# tablespoon-no-adc.net
KiCad netlist of a schematic drawn in EAGLE
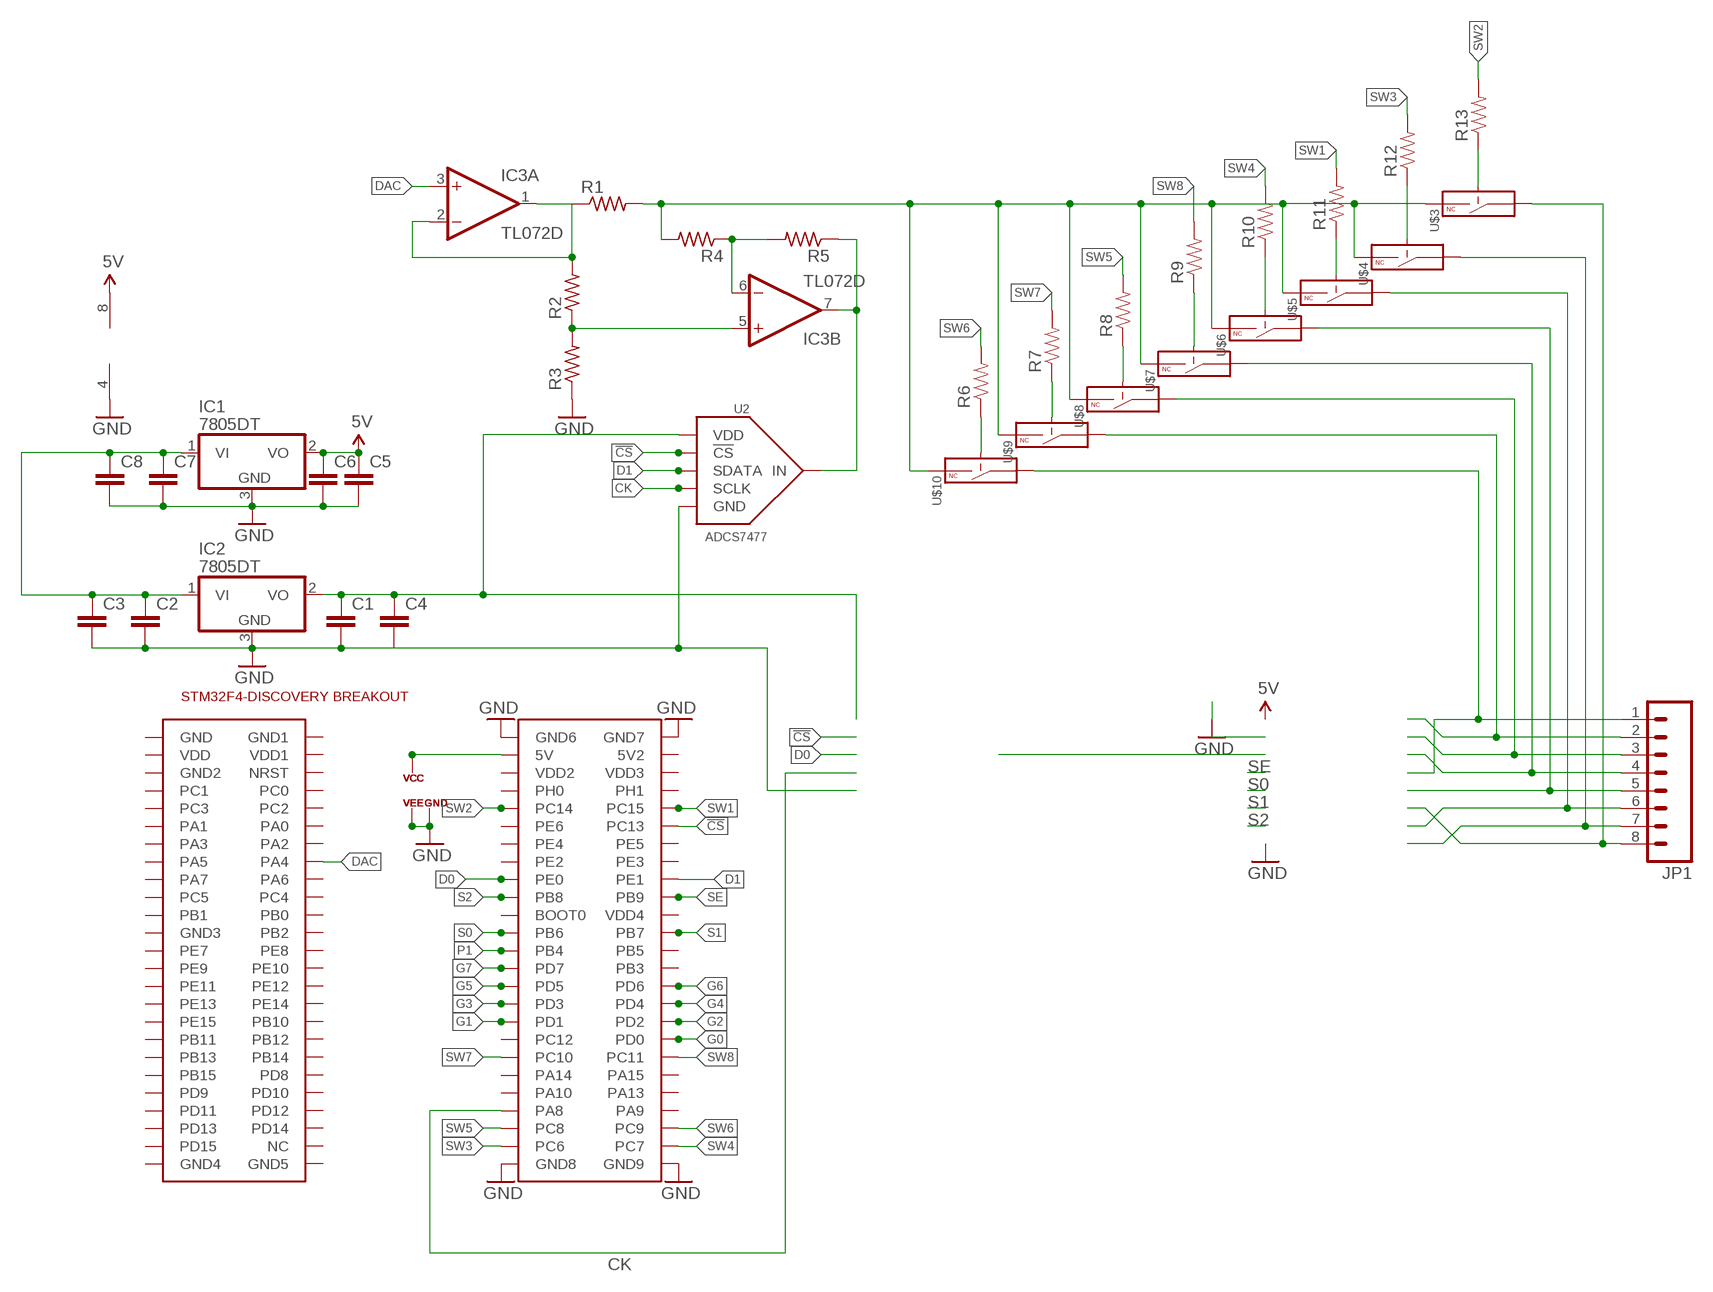
[diagram p0: schematic, sheet 1]

(export (version "E")
  (design (tool "Eeschema 10.0.6"))
  (components
    (comp (ref "C1")
      (value "C-EUC0805")
      (footprint "eagle-import:C0805")
      (libsource (lib "eagle-import") (part "C-EUC0805"))
    )
    (comp (ref "C2")
      (value "C-EUC0805")
      (footprint "eagle-import:C0805")
      (libsource (lib "eagle-import") (part "C-EUC0805"))
    )
    (comp (ref "C3")
      (value "C-EUC0805")
      (footprint "eagle-import:C0805")
      (libsource (lib "eagle-import") (part "C-EUC0805"))
    )
    (comp (ref "C4")
      (value "C-EUC0805")
      (footprint "eagle-import:C0805")
      (libsource (lib "eagle-import") (part "C-EUC0805"))
    )
    (comp (ref "C5")
      (value "C-EUC0805")
      (footprint "eagle-import:C0805")
      (libsource (lib "eagle-import") (part "C-EUC0805"))
    )
    (comp (ref "C6")
      (value "C-EUC0805")
      (footprint "eagle-import:C0805")
      (libsource (lib "eagle-import") (part "C-EUC0805"))
    )
    (comp (ref "C7")
      (value "C-EUC0805")
      (footprint "eagle-import:C0805")
      (libsource (lib "eagle-import") (part "C-EUC0805"))
    )
    (comp (ref "C8")
      (value "C-EUC0805")
      (footprint "eagle-import:C0805")
      (libsource (lib "eagle-import") (part "C-EUC0805"))
    )
    (comp (ref "IC1")
      (value "7805DT")
      (footprint "eagle-import:TO252")
      (libsource (lib "eagle-import") (part "78DT05"))
    )
    (comp (ref "IC2")
      (value "7805DT")
      (footprint "eagle-import:TO252")
      (libsource (lib "eagle-import") (part "78DT05"))
    )
    (comp (ref "IC3")
      (value "TL072D")
      (footprint "eagle-import:SO08")
      (libsource (lib "eagle-import") (part "TL072D"))
    )
    (comp (ref "JP1")
      (value "M08LONGPADS")
      (footprint "eagle-import:1X08_LONGPADS")
      (libsource (lib "eagle-import") (part "M08LONGPADS"))
    )
    (comp (ref "R1")
      (value "R-US_R0603")
      (footprint "eagle-import:R0603")
      (libsource (lib "eagle-import") (part "R-US_R0603"))
    )
    (comp (ref "R2")
      (value "R-US_R0603")
      (footprint "eagle-import:R0603")
      (libsource (lib "eagle-import") (part "R-US_R0603"))
    )
    (comp (ref "R3")
      (value "R-US_R0603")
      (footprint "eagle-import:R0603")
      (libsource (lib "eagle-import") (part "R-US_R0603"))
    )
    (comp (ref "R4")
      (value "R-US_R0603")
      (footprint "eagle-import:R0603")
      (libsource (lib "eagle-import") (part "R-US_R0603"))
    )
    (comp (ref "R5")
      (value "R-US_R0603")
      (footprint "eagle-import:R0603")
      (libsource (lib "eagle-import") (part "R-US_R0603"))
    )
    (comp (ref "R6")
      (value "RESISTOR0805-RES")
      (footprint "eagle-import:0805")
      (libsource (lib "eagle-import") (part "RESISTOR0805-RES"))
    )
    (comp (ref "R7")
      (value "RESISTOR0805-RES")
      (footprint "eagle-import:0805")
      (libsource (lib "eagle-import") (part "RESISTOR0805-RES"))
    )
    (comp (ref "R8")
      (value "RESISTOR0805-RES")
      (footprint "eagle-import:0805")
      (libsource (lib "eagle-import") (part "RESISTOR0805-RES"))
    )
    (comp (ref "R9")
      (value "RESISTOR0805-RES")
      (footprint "eagle-import:0805")
      (libsource (lib "eagle-import") (part "RESISTOR0805-RES"))
    )
    (comp (ref "R10")
      (value "RESISTOR0805-RES")
      (footprint "eagle-import:0805")
      (libsource (lib "eagle-import") (part "RESISTOR0805-RES"))
    )
    (comp (ref "R11")
      (value "RESISTOR0805-RES")
      (footprint "eagle-import:0805")
      (libsource (lib "eagle-import") (part "RESISTOR0805-RES"))
    )
    (comp (ref "R12")
      (value "RESISTOR0805-RES")
      (footprint "eagle-import:0805")
      (libsource (lib "eagle-import") (part "RESISTOR0805-RES"))
    )
    (comp (ref "R13")
      (value "RESISTOR0805-RES")
      (footprint "eagle-import:0805")
      (libsource (lib "eagle-import") (part "RESISTOR0805-RES"))
    )
    (comp (ref "U$1")
      (value "STM32F4-DISCOVERY")
      (footprint "eagle-import:STM32F4-DISCOVERY")
      (libsource (lib "eagle-import") (part "STM32F4-DISCOVERY"))
    )
    (comp (ref "U$3")
      (value "DG467")
      (footprint "eagle-import:TSSOP-6")
      (libsource (lib "eagle-import") (part "DG467"))
    )
    (comp (ref "U$4")
      (value "DG467")
      (footprint "eagle-import:TSSOP-6")
      (libsource (lib "eagle-import") (part "DG467"))
    )
    (comp (ref "U$5")
      (value "DG467")
      (footprint "eagle-import:TSSOP-6")
      (libsource (lib "eagle-import") (part "DG467"))
    )
    (comp (ref "U$6")
      (value "DG467")
      (footprint "eagle-import:TSSOP-6")
      (libsource (lib "eagle-import") (part "DG467"))
    )
    (comp (ref "U$7")
      (value "DG467")
      (footprint "eagle-import:TSSOP-6")
      (libsource (lib "eagle-import") (part "DG467"))
    )
    (comp (ref "U$8")
      (value "DG467")
      (footprint "eagle-import:TSSOP-6")
      (libsource (lib "eagle-import") (part "DG467"))
    )
    (comp (ref "U$9")
      (value "DG467")
      (footprint "eagle-import:TSSOP-6")
      (libsource (lib "eagle-import") (part "DG467"))
    )
    (comp (ref "U$10")
      (value "DG467")
      (footprint "eagle-import:TSSOP-6")
      (libsource (lib "eagle-import") (part "DG467"))
    )
    (comp (ref "U2")
      (value "ADCS7477")
      (footprint "eagle-import:SOT-23-6")
      (libsource (lib "eagle-import") (part "ADCS7477"))
    )
  )
  (nets
    (net (code "1") (name "/~{CS}") (class "Default")
      (node (ref "U$1") (pin "P$62") (pinfunction "PC13_P$62") (pintype "bidirectional"))
      (node (ref "U2") (pin "P$6") (pinfunction "~{CS}_P$6") (pintype "bidirectional"))
    )
    (net (code "2") (name "5V") (class "Default")
      (node (ref "C5") (pin "1") (pinfunction "1_1") (pintype "passive"))
      (node (ref "C6") (pin "1") (pinfunction "1_1") (pintype "passive"))
      (node (ref "IC1") (pin "2") (pinfunction "VO_2") (pintype "passive"))
      (node (ref "IC3") (pin "8") (pinfunction "V+_8") (pintype "power_in"))
    )
    (net (code "3") (name "CK") (class "Default")
      (node (ref "U$1") (pin "P$93") (pinfunction "PA8_P$93") (pintype "bidirectional"))
      (node (ref "U2") (pin "P$4") (pinfunction "SCLK_P$4") (pintype "bidirectional"))
    )
    (net (code "4") (name "D0") (class "Default")
      (node (ref "U$1") (pin "P$67") (pinfunction "PE0_P$67") (pintype "bidirectional"))
    )
    (net (code "5") (name "D1") (class "Default")
      (node (ref "U$1") (pin "P$68") (pinfunction "PE1_P$68") (pintype "bidirectional"))
      (node (ref "U2") (pin "P$5") (pinfunction "SDATA_P$5") (pintype "bidirectional"))
    )
    (net (code "6") (name "DAC") (class "Default")
      (node (ref "IC3") (pin "3") (pinfunction "+IN_3") (pintype "input"))
      (node (ref "U$1") (pin "P$16") (pinfunction "PA4_P$16") (pintype "bidirectional"))
    )
    (net (code "7") (name "G0") (class "Default")
      (node (ref "U$1") (pin "P$86") (pinfunction "PD0_P$86") (pintype "bidirectional"))
    )
    (net (code "8") (name "G1") (class "Default")
      (node (ref "U$1") (pin "P$83") (pinfunction "PD1_P$83") (pintype "bidirectional"))
    )
    (net (code "9") (name "G2") (class "Default")
      (node (ref "U$1") (pin "P$84") (pinfunction "PD2_P$84") (pintype "bidirectional"))
    )
    (net (code "10") (name "G3") (class "Default")
      (node (ref "U$1") (pin "P$81") (pinfunction "PD3_P$81") (pintype "bidirectional"))
    )
    (net (code "11") (name "G4") (class "Default")
      (node (ref "U$1") (pin "P$82") (pinfunction "PD4_P$82") (pintype "bidirectional"))
    )
    (net (code "12") (name "G5") (class "Default")
      (node (ref "U$1") (pin "P$79") (pinfunction "PD5_P$79") (pintype "bidirectional"))
    )
    (net (code "13") (name "G6") (class "Default")
      (node (ref "U$1") (pin "P$80") (pinfunction "PD6_P$80") (pintype "bidirectional"))
    )
    (net (code "14") (name "G7") (class "Default")
      (node (ref "U$1") (pin "P$77") (pinfunction "PD7_P$77") (pintype "bidirectional"))
    )
    (net (code "15") (name "GND") (class "Default")
      (node (ref "C1") (pin "2") (pinfunction "2_2") (pintype "passive"))
      (node (ref "C2") (pin "2") (pinfunction "2_2") (pintype "passive"))
      (node (ref "C3") (pin "2") (pinfunction "2_2") (pintype "passive"))
      (node (ref "C4") (pin "2") (pinfunction "2_2") (pintype "passive"))
      (node (ref "C5") (pin "2") (pinfunction "2_2") (pintype "passive"))
      (node (ref "C6") (pin "2") (pinfunction "2_2") (pintype "passive"))
      (node (ref "C7") (pin "2") (pinfunction "2_2") (pintype "passive"))
      (node (ref "C8") (pin "2") (pinfunction "2_2") (pintype "passive"))
      (node (ref "IC1") (pin "3") (pinfunction "GND_3") (pintype "passive"))
      (node (ref "IC2") (pin "3") (pinfunction "GND_3") (pintype "passive"))
      (node (ref "IC3") (pin "4") (pinfunction "V-_4") (pintype "power_in"))
      (node (ref "R3") (pin "1") (pinfunction "1_1") (pintype "passive"))
      (node (ref "U$1") (pin "P$100") (pinfunction "GND9_P$100") (pintype "bidirectional"))
      (node (ref "U$1") (pin "P$51") (pinfunction "GND6_P$51") (pintype "bidirectional"))
      (node (ref "U$1") (pin "P$52") (pinfunction "GND7_P$52") (pintype "bidirectional"))
      (node (ref "U$1") (pin "P$99") (pinfunction "GND8_P$99") (pintype "bidirectional"))
      (node (ref "U$10") (pin "P$2") (pinfunction "VEE_P$2") (pintype "bidirectional"))
      (node (ref "U$10") (pin "P$4") (pinfunction "GND_P$4") (pintype "bidirectional"))
      (node (ref "U$3") (pin "P$2") (pinfunction "VEE_P$2") (pintype "bidirectional"))
      (node (ref "U$3") (pin "P$4") (pinfunction "GND_P$4") (pintype "bidirectional"))
      (node (ref "U$4") (pin "P$2") (pinfunction "VEE_P$2") (pintype "bidirectional"))
      (node (ref "U$4") (pin "P$4") (pinfunction "GND_P$4") (pintype "bidirectional"))
      (node (ref "U$5") (pin "P$2") (pinfunction "VEE_P$2") (pintype "bidirectional"))
      (node (ref "U$5") (pin "P$4") (pinfunction "GND_P$4") (pintype "bidirectional"))
      (node (ref "U$6") (pin "P$2") (pinfunction "VEE_P$2") (pintype "bidirectional"))
      (node (ref "U$6") (pin "P$4") (pinfunction "GND_P$4") (pintype "bidirectional"))
      (node (ref "U$7") (pin "P$2") (pinfunction "VEE_P$2") (pintype "bidirectional"))
      (node (ref "U$7") (pin "P$4") (pinfunction "GND_P$4") (pintype "bidirectional"))
      (node (ref "U$8") (pin "P$2") (pinfunction "VEE_P$2") (pintype "bidirectional"))
      (node (ref "U$8") (pin "P$4") (pinfunction "GND_P$4") (pintype "bidirectional"))
      (node (ref "U$9") (pin "P$2") (pinfunction "VEE_P$2") (pintype "bidirectional"))
      (node (ref "U$9") (pin "P$4") (pinfunction "GND_P$4") (pintype "bidirectional"))
      (node (ref "U2") (pin "P$2") (pinfunction "GND_P$2") (pintype "bidirectional"))
    )
    (net (code "16") (name "Net-(IC1-VI)") (class "Default")
      (node (ref "C2") (pin "1") (pinfunction "1_1") (pintype "passive"))
      (node (ref "C3") (pin "1") (pinfunction "1_1") (pintype "passive"))
      (node (ref "C7") (pin "1") (pinfunction "1_1") (pintype "passive"))
      (node (ref "C8") (pin "1") (pinfunction "1_1") (pintype "passive"))
      (node (ref "IC1") (pin "1") (pinfunction "VI_1") (pintype "input"))
      (node (ref "IC2") (pin "1") (pinfunction "VI_1") (pintype "input"))
    )
    (net (code "17") (name "Net-(IC2-VO)") (class "Default")
      (node (ref "C1") (pin "1") (pinfunction "1_1") (pintype "passive"))
      (node (ref "C4") (pin "1") (pinfunction "1_1") (pintype "passive"))
      (node (ref "IC2") (pin "2") (pinfunction "VO_2") (pintype "passive"))
      (node (ref "U2") (pin "P$1") (pinfunction "VDD_P$1") (pintype "bidirectional"))
    )
    (net (code "18") (name "Net-(IC3A--IN)") (class "Default")
      (node (ref "IC3") (pin "1") (pinfunction "OUT_1") (pintype "output"))
      (node (ref "IC3") (pin "2") (pinfunction "-IN_2") (pintype "input"))
      (node (ref "R1") (pin "1") (pinfunction "1_1") (pintype "passive"))
      (node (ref "R2") (pin "2") (pinfunction "2_2") (pintype "passive"))
    )
    (net (code "19") (name "Net-(IC3B-+IN)") (class "Default")
      (node (ref "IC3") (pin "5") (pinfunction "+IN_5") (pintype "input"))
      (node (ref "R2") (pin "1") (pinfunction "1_1") (pintype "passive"))
      (node (ref "R3") (pin "2") (pinfunction "2_2") (pintype "passive"))
    )
    (net (code "20") (name "Net-(IC3B--IN)") (class "Default")
      (node (ref "IC3") (pin "6") (pinfunction "-IN_6") (pintype "input"))
      (node (ref "R4") (pin "1") (pinfunction "1_1") (pintype "passive"))
      (node (ref "R5") (pin "2") (pinfunction "2_2") (pintype "passive"))
    )
    (net (code "21") (name "Net-(IC3B-OUT)") (class "Default")
      (node (ref "IC3") (pin "7") (pinfunction "OUT_7") (pintype "output"))
      (node (ref "R5") (pin "1") (pinfunction "1_1") (pintype "passive"))
      (node (ref "U2") (pin "P$3") (pinfunction "IN_P$3") (pintype "bidirectional"))
    )
    (net (code "22") (name "Net-(U$1-5V)") (class "Default")
      (node (ref "U$1") (pin "P$53") (pinfunction "5V_P$53") (pintype "bidirectional"))
      (node (ref "U$10") (pin "P$5") (pinfunction "VCC_P$5") (pintype "bidirectional"))
      (node (ref "U$3") (pin "P$5") (pinfunction "VCC_P$5") (pintype "bidirectional"))
      (node (ref "U$4") (pin "P$5") (pinfunction "VCC_P$5") (pintype "bidirectional"))
      (node (ref "U$5") (pin "P$5") (pinfunction "VCC_P$5") (pintype "bidirectional"))
      (node (ref "U$6") (pin "P$5") (pinfunction "VCC_P$5") (pintype "bidirectional"))
      (node (ref "U$7") (pin "P$5") (pinfunction "VCC_P$5") (pintype "bidirectional"))
      (node (ref "U$8") (pin "P$5") (pinfunction "VCC_P$5") (pintype "bidirectional"))
      (node (ref "U$9") (pin "P$5") (pinfunction "VCC_P$5") (pintype "bidirectional"))
    )
    (net (code "23") (name "Net-(U$3A-COM)") (class "Default")
      (node (ref "JP1") (pin "8") (pinfunction "8_8") (pintype "passive"))
      (node (ref "U$3") (pin "P$6") (pinfunction "COM_P$6") (pintype "bidirectional"))
    )
    (net (code "24") (name "Net-(U$3A-CTL)") (class "Default")
      (node (ref "R13") (pin "1") (pinfunction "1_1") (pintype "passive"))
      (node (ref "U$3") (pin "P$3") (pinfunction "CTL_P$3") (pintype "bidirectional"))
    )
    (net (code "25") (name "Net-(U$4A-COM)") (class "Default")
      (node (ref "JP1") (pin "7") (pinfunction "7_7") (pintype "passive"))
      (node (ref "U$4") (pin "P$6") (pinfunction "COM_P$6") (pintype "bidirectional"))
    )
    (net (code "26") (name "Net-(U$4A-CTL)") (class "Default")
      (node (ref "R12") (pin "1") (pinfunction "1_1") (pintype "passive"))
      (node (ref "U$4") (pin "P$3") (pinfunction "CTL_P$3") (pintype "bidirectional"))
    )
    (net (code "27") (name "Net-(U$5A-COM)") (class "Default")
      (node (ref "JP1") (pin "6") (pinfunction "6_6") (pintype "passive"))
      (node (ref "U$5") (pin "P$6") (pinfunction "COM_P$6") (pintype "bidirectional"))
    )
    (net (code "28") (name "Net-(U$5A-CTL)") (class "Default")
      (node (ref "R11") (pin "1") (pinfunction "1_1") (pintype "passive"))
      (node (ref "U$5") (pin "P$3") (pinfunction "CTL_P$3") (pintype "bidirectional"))
    )
    (net (code "29") (name "Net-(U$6A-COM)") (class "Default")
      (node (ref "JP1") (pin "5") (pinfunction "5_5") (pintype "passive"))
      (node (ref "U$6") (pin "P$6") (pinfunction "COM_P$6") (pintype "bidirectional"))
    )
    (net (code "30") (name "Net-(U$6A-CTL)") (class "Default")
      (node (ref "R10") (pin "1") (pinfunction "1_1") (pintype "passive"))
      (node (ref "U$6") (pin "P$3") (pinfunction "CTL_P$3") (pintype "bidirectional"))
    )
    (net (code "31") (name "Net-(U$7A-COM)") (class "Default")
      (node (ref "JP1") (pin "4") (pinfunction "4_4") (pintype "passive"))
      (node (ref "U$7") (pin "P$6") (pinfunction "COM_P$6") (pintype "bidirectional"))
    )
    (net (code "32") (name "Net-(U$7A-CTL)") (class "Default")
      (node (ref "R9") (pin "1") (pinfunction "1_1") (pintype "passive"))
      (node (ref "U$7") (pin "P$3") (pinfunction "CTL_P$3") (pintype "bidirectional"))
    )
    (net (code "33") (name "Net-(U$8A-COM)") (class "Default")
      (node (ref "JP1") (pin "3") (pinfunction "3_3") (pintype "passive"))
      (node (ref "U$8") (pin "P$6") (pinfunction "COM_P$6") (pintype "bidirectional"))
    )
    (net (code "34") (name "Net-(U$8A-CTL)") (class "Default")
      (node (ref "R8") (pin "1") (pinfunction "1_1") (pintype "passive"))
      (node (ref "U$8") (pin "P$3") (pinfunction "CTL_P$3") (pintype "bidirectional"))
    )
    (net (code "35") (name "Net-(U$9A-COM)") (class "Default")
      (node (ref "JP1") (pin "2") (pinfunction "2_2") (pintype "passive"))
      (node (ref "U$9") (pin "P$6") (pinfunction "COM_P$6") (pintype "bidirectional"))
    )
    (net (code "36") (name "Net-(U$9A-CTL)") (class "Default")
      (node (ref "R7") (pin "1") (pinfunction "1_1") (pintype "passive"))
      (node (ref "U$9") (pin "P$3") (pinfunction "CTL_P$3") (pintype "bidirectional"))
    )
    (net (code "37") (name "Net-(U$10A-COM)") (class "Default")
      (node (ref "JP1") (pin "1") (pinfunction "1_1") (pintype "passive"))
      (node (ref "U$10") (pin "P$6") (pinfunction "COM_P$6") (pintype "bidirectional"))
    )
    (net (code "38") (name "Net-(U$10A-CTL)") (class "Default")
      (node (ref "R6") (pin "1") (pinfunction "1_1") (pintype "passive"))
      (node (ref "U$10") (pin "P$3") (pinfunction "CTL_P$3") (pintype "bidirectional"))
    )
    (net (code "39") (name "Net-(U$10A-IN)") (class "Default")
      (node (ref "R1") (pin "2") (pinfunction "2_2") (pintype "passive"))
      (node (ref "R4") (pin "2") (pinfunction "2_2") (pintype "passive"))
      (node (ref "U$10") (pin "P$1") (pinfunction "IN_P$1") (pintype "bidirectional"))
      (node (ref "U$3") (pin "P$1") (pinfunction "IN_P$1") (pintype "bidirectional"))
      (node (ref "U$4") (pin "P$1") (pinfunction "IN_P$1") (pintype "bidirectional"))
      (node (ref "U$5") (pin "P$1") (pinfunction "IN_P$1") (pintype "bidirectional"))
      (node (ref "U$6") (pin "P$1") (pinfunction "IN_P$1") (pintype "bidirectional"))
      (node (ref "U$7") (pin "P$1") (pinfunction "IN_P$1") (pintype "bidirectional"))
      (node (ref "U$8") (pin "P$1") (pinfunction "IN_P$1") (pintype "bidirectional"))
      (node (ref "U$9") (pin "P$1") (pinfunction "IN_P$1") (pintype "bidirectional"))
    )
    (net (code "40") (name "P1") (class "Default")
      (node (ref "U$1") (pin "P$75") (pinfunction "PB4_P$75") (pintype "bidirectional"))
    )
    (net (code "41") (name "S0") (class "Default")
      (node (ref "U$1") (pin "P$73") (pinfunction "PB6_P$73") (pintype "bidirectional"))
    )
    (net (code "42") (name "S1") (class "Default")
      (node (ref "U$1") (pin "P$74") (pinfunction "PB7_P$74") (pintype "bidirectional"))
    )
    (net (code "43") (name "S2") (class "Default")
      (node (ref "U$1") (pin "P$69") (pinfunction "PB8_P$69") (pintype "bidirectional"))
    )
    (net (code "44") (name "SE") (class "Default")
      (node (ref "U$1") (pin "P$70") (pinfunction "PB9_P$70") (pintype "bidirectional"))
    )
    (net (code "45") (name "SW1") (class "Default")
      (node (ref "R11") (pin "2") (pinfunction "2_2") (pintype "passive"))
      (node (ref "U$1") (pin "P$60") (pinfunction "PC15_P$60") (pintype "bidirectional"))
    )
    (net (code "46") (name "SW2") (class "Default")
      (node (ref "R13") (pin "2") (pinfunction "2_2") (pintype "passive"))
      (node (ref "U$1") (pin "P$59") (pinfunction "PC14_P$59") (pintype "bidirectional"))
    )
    (net (code "47") (name "SW3") (class "Default")
      (node (ref "R12") (pin "2") (pinfunction "2_2") (pintype "passive"))
      (node (ref "U$1") (pin "P$97") (pinfunction "PC6_P$97") (pintype "bidirectional"))
    )
    (net (code "48") (name "SW4") (class "Default")
      (node (ref "R10") (pin "2") (pinfunction "2_2") (pintype "passive"))
      (node (ref "U$1") (pin "P$98") (pinfunction "PC7_P$98") (pintype "bidirectional"))
    )
    (net (code "49") (name "SW5") (class "Default")
      (node (ref "R8") (pin "2") (pinfunction "2_2") (pintype "passive"))
      (node (ref "U$1") (pin "P$95") (pinfunction "PC8_P$95") (pintype "bidirectional"))
    )
    (net (code "50") (name "SW6") (class "Default")
      (node (ref "R6") (pin "2") (pinfunction "2_2") (pintype "passive"))
      (node (ref "U$1") (pin "P$96") (pinfunction "PC9_P$96") (pintype "bidirectional"))
    )
    (net (code "51") (name "SW7") (class "Default")
      (node (ref "R7") (pin "2") (pinfunction "2_2") (pintype "passive"))
      (node (ref "U$1") (pin "P$87") (pinfunction "PC10_P$87") (pintype "bidirectional"))
    )
    (net (code "52") (name "SW8") (class "Default")
      (node (ref "R9") (pin "2") (pinfunction "2_2") (pintype "passive"))
      (node (ref "U$1") (pin "P$88") (pinfunction "PC11_P$88") (pintype "bidirectional"))
    )
    (net (code "53") (name "unconnected-(U$1-5V2-PadP$54)") (class "Default")
      (node (ref "U$1") (pin "P$54") (pinfunction "5V2_P$54") (pintype "bidirectional"))
    )
    (net (code "54") (name "unconnected-(U$1-BOOT0-PadP$71)") (class "Default")
      (node (ref "U$1") (pin "P$71") (pinfunction "BOOT0_P$71") (pintype "bidirectional"))
    )
    (net (code "55") (name "unconnected-(U$1-GND-PadP$1)") (class "Default")
      (node (ref "U$1") (pin "P$1") (pinfunction "GND_P$1") (pintype "bidirectional"))
    )
    (net (code "56") (name "unconnected-(U$1-GND1-PadP$2)") (class "Default")
      (node (ref "U$1") (pin "P$2") (pinfunction "GND1_P$2") (pintype "bidirectional"))
    )
    (net (code "57") (name "unconnected-(U$1-GND2-PadP$5)") (class "Default")
      (node (ref "U$1") (pin "P$5") (pinfunction "GND2_P$5") (pintype "bidirectional"))
    )
    (net (code "58") (name "unconnected-(U$1-GND3-PadP$23)") (class "Default")
      (node (ref "U$1") (pin "P$23") (pinfunction "GND3_P$23") (pintype "bidirectional"))
    )
    (net (code "59") (name "unconnected-(U$1-GND4-PadP$49)") (class "Default")
      (node (ref "U$1") (pin "P$49") (pinfunction "GND4_P$49") (pintype "bidirectional"))
    )
    (net (code "60") (name "unconnected-(U$1-GND5-PadP$50)") (class "Default")
      (node (ref "U$1") (pin "P$50") (pinfunction "GND5_P$50") (pintype "bidirectional"))
    )
    (net (code "61") (name "unconnected-(U$1-NC-PadP$48)") (class "Default")
      (node (ref "U$1") (pin "P$48") (pinfunction "NC_P$48") (pintype "bidirectional"))
    )
    (net (code "62") (name "unconnected-(U$1-NRST-PadP$6)") (class "Default")
      (node (ref "U$1") (pin "P$6") (pinfunction "NRST_P$6") (pintype "bidirectional"))
    )
    (net (code "63") (name "unconnected-(U$1-PA0-PadP$12)") (class "Default")
      (node (ref "U$1") (pin "P$12") (pinfunction "PA0_P$12") (pintype "bidirectional"))
    )
    (net (code "64") (name "unconnected-(U$1-PA1-PadP$11)") (class "Default")
      (node (ref "U$1") (pin "P$11") (pinfunction "PA1_P$11") (pintype "bidirectional"))
    )
    (net (code "65") (name "unconnected-(U$1-PA2-PadP$14)") (class "Default")
      (node (ref "U$1") (pin "P$14") (pinfunction "PA2_P$14") (pintype "bidirectional"))
    )
    (net (code "66") (name "unconnected-(U$1-PA3-PadP$13)") (class "Default")
      (node (ref "U$1") (pin "P$13") (pinfunction "PA3_P$13") (pintype "bidirectional"))
    )
    (net (code "67") (name "unconnected-(U$1-PA5-PadP$15)") (class "Default")
      (node (ref "U$1") (pin "P$15") (pinfunction "PA5_P$15") (pintype "bidirectional"))
    )
    (net (code "68") (name "unconnected-(U$1-PA6-PadP$18)") (class "Default")
      (node (ref "U$1") (pin "P$18") (pinfunction "PA6_P$18") (pintype "bidirectional"))
    )
    (net (code "69") (name "unconnected-(U$1-PA7-PadP$17)") (class "Default")
      (node (ref "U$1") (pin "P$17") (pinfunction "PA7_P$17") (pintype "bidirectional"))
    )
    (net (code "70") (name "unconnected-(U$1-PA9-PadP$94)") (class "Default")
      (node (ref "U$1") (pin "P$94") (pinfunction "PA9_P$94") (pintype "bidirectional"))
    )
    (net (code "71") (name "unconnected-(U$1-PA10-PadP$91)") (class "Default")
      (node (ref "U$1") (pin "P$91") (pinfunction "PA10_P$91") (pintype "bidirectional"))
    )
    (net (code "72") (name "unconnected-(U$1-PA13-PadP$92)") (class "Default")
      (node (ref "U$1") (pin "P$92") (pinfunction "PA13_P$92") (pintype "bidirectional"))
    )
    (net (code "73") (name "unconnected-(U$1-PA14-PadP$89)") (class "Default")
      (node (ref "U$1") (pin "P$89") (pinfunction "PA14_P$89") (pintype "bidirectional"))
    )
    (net (code "74") (name "unconnected-(U$1-PA15-PadP$90)") (class "Default")
      (node (ref "U$1") (pin "P$90") (pinfunction "PA15_P$90") (pintype "bidirectional"))
    )
    (net (code "75") (name "unconnected-(U$1-PB0-PadP$22)") (class "Default")
      (node (ref "U$1") (pin "P$22") (pinfunction "PB0_P$22") (pintype "bidirectional"))
    )
    (net (code "76") (name "unconnected-(U$1-PB1-PadP$21)") (class "Default")
      (node (ref "U$1") (pin "P$21") (pinfunction "PB1_P$21") (pintype "bidirectional"))
    )
    (net (code "77") (name "unconnected-(U$1-PB2-PadP$24)") (class "Default")
      (node (ref "U$1") (pin "P$24") (pinfunction "PB2_P$24") (pintype "bidirectional"))
    )
    (net (code "78") (name "unconnected-(U$1-PB3-PadP$78)") (class "Default")
      (node (ref "U$1") (pin "P$78") (pinfunction "PB3_P$78") (pintype "bidirectional"))
    )
    (net (code "79") (name "unconnected-(U$1-PB5-PadP$76)") (class "Default")
      (node (ref "U$1") (pin "P$76") (pinfunction "PB5_P$76") (pintype "bidirectional"))
    )
    (net (code "80") (name "unconnected-(U$1-PB10-PadP$34)") (class "Default")
      (node (ref "U$1") (pin "P$34") (pinfunction "PB10_P$34") (pintype "bidirectional"))
    )
    (net (code "81") (name "unconnected-(U$1-PB11-PadP$35)") (class "Default")
      (node (ref "U$1") (pin "P$35") (pinfunction "PB11_P$35") (pintype "bidirectional"))
    )
    (net (code "82") (name "unconnected-(U$1-PB12-PadP$36)") (class "Default")
      (node (ref "U$1") (pin "P$36") (pinfunction "PB12_P$36") (pintype "bidirectional"))
    )
    (net (code "83") (name "unconnected-(U$1-PB13-PadP$37)") (class "Default")
      (node (ref "U$1") (pin "P$37") (pinfunction "PB13_P$37") (pintype "bidirectional"))
    )
    (net (code "84") (name "unconnected-(U$1-PB14-PadP$38)") (class "Default")
      (node (ref "U$1") (pin "P$38") (pinfunction "PB14_P$38") (pintype "bidirectional"))
    )
    (net (code "85") (name "unconnected-(U$1-PB15-PadP$39)") (class "Default")
      (node (ref "U$1") (pin "P$39") (pinfunction "PB15_P$39") (pintype "bidirectional"))
    )
    (net (code "86") (name "unconnected-(U$1-PC0-PadP$8)") (class "Default")
      (node (ref "U$1") (pin "P$8") (pinfunction "PC0_P$8") (pintype "bidirectional"))
    )
    (net (code "87") (name "unconnected-(U$1-PC1-PadP$7)") (class "Default")
      (node (ref "U$1") (pin "P$7") (pinfunction "PC1_P$7") (pintype "bidirectional"))
    )
    (net (code "88") (name "unconnected-(U$1-PC2-PadP$10)") (class "Default")
      (node (ref "U$1") (pin "P$10") (pinfunction "PC2_P$10") (pintype "bidirectional"))
    )
    (net (code "89") (name "unconnected-(U$1-PC3-PadP$9)") (class "Default")
      (node (ref "U$1") (pin "P$9") (pinfunction "PC3_P$9") (pintype "bidirectional"))
    )
    (net (code "90") (name "unconnected-(U$1-PC4-PadP$20)") (class "Default")
      (node (ref "U$1") (pin "P$20") (pinfunction "PC4_P$20") (pintype "bidirectional"))
    )
    (net (code "91") (name "unconnected-(U$1-PC5-PadP$19)") (class "Default")
      (node (ref "U$1") (pin "P$19") (pinfunction "PC5_P$19") (pintype "bidirectional"))
    )
    (net (code "92") (name "unconnected-(U$1-PC12-PadP$85)") (class "Default")
      (node (ref "U$1") (pin "P$85") (pinfunction "PC12_P$85") (pintype "bidirectional"))
    )
    (net (code "93") (name "unconnected-(U$1-PD8-PadP$40)") (class "Default")
      (node (ref "U$1") (pin "P$40") (pinfunction "PD8_P$40") (pintype "bidirectional"))
    )
    (net (code "94") (name "unconnected-(U$1-PD9-PadP$41)") (class "Default")
      (node (ref "U$1") (pin "P$41") (pinfunction "PD9_P$41") (pintype "bidirectional"))
    )
    (net (code "95") (name "unconnected-(U$1-PD10-PadP$42)") (class "Default")
      (node (ref "U$1") (pin "P$42") (pinfunction "PD10_P$42") (pintype "bidirectional"))
    )
    (net (code "96") (name "unconnected-(U$1-PD11-PadP$43)") (class "Default")
      (node (ref "U$1") (pin "P$43") (pinfunction "PD11_P$43") (pintype "bidirectional"))
    )
    (net (code "97") (name "unconnected-(U$1-PD12-PadP$44)") (class "Default")
      (node (ref "U$1") (pin "P$44") (pinfunction "PD12_P$44") (pintype "bidirectional"))
    )
    (net (code "98") (name "unconnected-(U$1-PD13-PadP$45)") (class "Default")
      (node (ref "U$1") (pin "P$45") (pinfunction "PD13_P$45") (pintype "bidirectional"))
    )
    (net (code "99") (name "unconnected-(U$1-PD14-PadP$46)") (class "Default")
      (node (ref "U$1") (pin "P$46") (pinfunction "PD14_P$46") (pintype "bidirectional"))
    )
    (net (code "100") (name "unconnected-(U$1-PD15-PadP$47)") (class "Default")
      (node (ref "U$1") (pin "P$47") (pinfunction "PD15_P$47") (pintype "bidirectional"))
    )
    (net (code "101") (name "unconnected-(U$1-PE2-PadP$65)") (class "Default")
      (node (ref "U$1") (pin "P$65") (pinfunction "PE2_P$65") (pintype "bidirectional"))
    )
    (net (code "102") (name "unconnected-(U$1-PE3-PadP$66)") (class "Default")
      (node (ref "U$1") (pin "P$66") (pinfunction "PE3_P$66") (pintype "bidirectional"))
    )
    (net (code "103") (name "unconnected-(U$1-PE4-PadP$63)") (class "Default")
      (node (ref "U$1") (pin "P$63") (pinfunction "PE4_P$63") (pintype "bidirectional"))
    )
    (net (code "104") (name "unconnected-(U$1-PE5-PadP$64)") (class "Default")
      (node (ref "U$1") (pin "P$64") (pinfunction "PE5_P$64") (pintype "bidirectional"))
    )
    (net (code "105") (name "unconnected-(U$1-PE6-PadP$61)") (class "Default")
      (node (ref "U$1") (pin "P$61") (pinfunction "PE6_P$61") (pintype "bidirectional"))
    )
    (net (code "106") (name "unconnected-(U$1-PE7-PadP$25)") (class "Default")
      (node (ref "U$1") (pin "P$25") (pinfunction "PE7_P$25") (pintype "bidirectional"))
    )
    (net (code "107") (name "unconnected-(U$1-PE8-PadP$26)") (class "Default")
      (node (ref "U$1") (pin "P$26") (pinfunction "PE8_P$26") (pintype "bidirectional"))
    )
    (net (code "108") (name "unconnected-(U$1-PE9-PadP$27)") (class "Default")
      (node (ref "U$1") (pin "P$27") (pinfunction "PE9_P$27") (pintype "bidirectional"))
    )
    (net (code "109") (name "unconnected-(U$1-PE10-PadP$28)") (class "Default")
      (node (ref "U$1") (pin "P$28") (pinfunction "PE10_P$28") (pintype "bidirectional"))
    )
    (net (code "110") (name "unconnected-(U$1-PE11-PadP$29)") (class "Default")
      (node (ref "U$1") (pin "P$29") (pinfunction "PE11_P$29") (pintype "bidirectional"))
    )
    (net (code "111") (name "unconnected-(U$1-PE12-PadP$30)") (class "Default")
      (node (ref "U$1") (pin "P$30") (pinfunction "PE12_P$30") (pintype "bidirectional"))
    )
    (net (code "112") (name "unconnected-(U$1-PE13-PadP$31)") (class "Default")
      (node (ref "U$1") (pin "P$31") (pinfunction "PE13_P$31") (pintype "bidirectional"))
    )
    (net (code "113") (name "unconnected-(U$1-PE14-PadP$32)") (class "Default")
      (node (ref "U$1") (pin "P$32") (pinfunction "PE14_P$32") (pintype "bidirectional"))
    )
    (net (code "114") (name "unconnected-(U$1-PE15-PadP$33)") (class "Default")
      (node (ref "U$1") (pin "P$33") (pinfunction "PE15_P$33") (pintype "bidirectional"))
    )
    (net (code "115") (name "unconnected-(U$1-PH0-PadP$57)") (class "Default")
      (node (ref "U$1") (pin "P$57") (pinfunction "PH0_P$57") (pintype "bidirectional"))
    )
    (net (code "116") (name "unconnected-(U$1-PH1-PadP$58)") (class "Default")
      (node (ref "U$1") (pin "P$58") (pinfunction "PH1_P$58") (pintype "bidirectional"))
    )
    (net (code "117") (name "unconnected-(U$1-VDD-PadP$3)") (class "Default")
      (node (ref "U$1") (pin "P$3") (pinfunction "VDD_P$3") (pintype "bidirectional"))
    )
    (net (code "118") (name "unconnected-(U$1-VDD1-PadP$4)") (class "Default")
      (node (ref "U$1") (pin "P$4") (pinfunction "VDD1_P$4") (pintype "bidirectional"))
    )
    (net (code "119") (name "unconnected-(U$1-VDD2-PadP$55)") (class "Default")
      (node (ref "U$1") (pin "P$55") (pinfunction "VDD2_P$55") (pintype "bidirectional"))
    )
    (net (code "120") (name "unconnected-(U$1-VDD3-PadP$56)") (class "Default")
      (node (ref "U$1") (pin "P$56") (pinfunction "VDD3_P$56") (pintype "bidirectional"))
    )
    (net (code "121") (name "unconnected-(U$1-VDD4-PadP$72)") (class "Default")
      (node (ref "U$1") (pin "P$72") (pinfunction "VDD4_P$72") (pintype "bidirectional"))
    )
  )
)
